# RX_Balun.net
KiCad netlist of a schematic drawn in Altium Designer
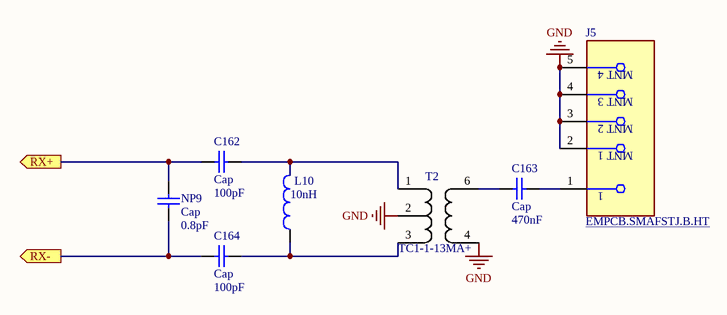
[diagram p0: RX Balun.SchDoc]

(export (version "E")
  (design (tool "Eeschema 10.0.6"))
  (components
    (comp (ref "C162")
      (value "Cap")
      (footprint "0402-A")
      (description "Capacitor")
      (fields (field (name "ALTIUM_VALUE") "100pF") (field (name "PUBLISHER") "Altium Limited"))
      (libsource (lib "Miscellaneous Devices") (part "Cap"))
    )
    (comp (ref "C163")
      (value "Cap")
      (footprint "0402-A")
      (description "Capacitor")
      (fields (field (name "ALTIUM_VALUE") "470nF") (field (name "PUBLISHER") "Altium Limited"))
      (libsource (lib "Miscellaneous Devices") (part "Cap"))
    )
    (comp (ref "C164")
      (value "Cap")
      (footprint "0402-A")
      (description "Capacitor")
      (fields (field (name "ALTIUM_VALUE") "100pF") (field (name "PUBLISHER") "Altium Limited"))
      (libsource (lib "Miscellaneous Devices") (part "Cap"))
    )
    (comp (ref "J5")
      (value "EMPCB.SMAFSTJ.B.HT")
      (footprint "FP-EMPCB_SMAFSTJ_B_HT-MFG")
      (description "CONN SMA JACK STR 50OHM EDGE MNT")
      (fields
        (field (name "OCTOPART") "https://octopart.com/empcb.smafstj.b.ht-taoglas-24204431")
        (field (name "MANUFACTURER") "Taoglas Limited")
      )
      (libsource (lib "Altium Content Vault") (part "c65b8a639cdaef1819ea20b5466f8fa"))
    )
    (comp (ref "L10")
      (value "10nH")
      (footprint "1608[0603]")
      (description "Inductor")
      (fields (field (name "PUBLISHER") "Altium Limited"))
      (libsource (lib "Miscellaneous Devices") (part "Inductor"))
    )
    (comp (ref "NP9")
      (value "Cap")
      (footprint "0402-A")
      (description "Capacitor")
      (fields (field (name "ALTIUM_VALUE") "0.8pF") (field (name "PUBLISHER") "Altium Limited"))
      (libsource (lib "Miscellaneous Devices") (part "Cap"))
    )
    (comp (ref "T2")
      (value "TC1-1-13MA+")
      (footprint "TC1-1-13MA+")
      (libsource (lib "TC1-1-13MA+") (part "TC1-1-13MA+"))
    )
  )
  (nets
    (net (code "1") (name "/RX+") (class "Default")
      (node (ref "C162") (pin "1") (pinfunction "1_1") (pintype "passive"))
      (node (ref "NP9") (pin "1") (pinfunction "1_1") (pintype "passive"))
    )
    (net (code "2") (name "/RX-") (class "Default")
      (node (ref "C164") (pin "1") (pinfunction "1_1") (pintype "passive"))
      (node (ref "NP9") (pin "2") (pinfunction "2_2") (pintype "passive"))
    )
    (net (code "3") (name "GND") (class "Default")
      (node (ref "J5") (pin "2") (pinfunction "MNT_1_2") (pintype "passive"))
      (node (ref "J5") (pin "3") (pinfunction "MNT_2_3") (pintype "passive"))
      (node (ref "J5") (pin "4") (pinfunction "MNT_3_4") (pintype "passive"))
      (node (ref "J5") (pin "5") (pinfunction "MNT_4_5") (pintype "passive"))
      (node (ref "T2") (pin "2") (pintype "passive"))
      (node (ref "T2") (pin "4") (pintype "passive"))
    )
    (net (code "4") (name "Net-(C162-Pad2)") (class "Default")
      (node (ref "C162") (pin "2") (pinfunction "2_2") (pintype "passive"))
      (node (ref "L10") (pin "2") (pinfunction "2_2") (pintype "passive"))
      (node (ref "T2") (pin "1") (pintype "passive"))
    )
    (net (code "5") (name "Net-(C163-Pad1)") (class "Default")
      (node (ref "C163") (pin "1") (pinfunction "1_1") (pintype "passive"))
      (node (ref "T2") (pin "6") (pintype "passive"))
    )
    (net (code "6") (name "Net-(C163-Pad2)") (class "Default")
      (node (ref "C163") (pin "2") (pinfunction "2_2") (pintype "passive"))
      (node (ref "J5") (pin "1") (pinfunction "1_1") (pintype "passive"))
    )
    (net (code "7") (name "Net-(C164-Pad2)") (class "Default")
      (node (ref "C164") (pin "2") (pinfunction "2_2") (pintype "passive"))
      (node (ref "L10") (pin "1") (pinfunction "1_1") (pintype "passive"))
      (node (ref "T2") (pin "3") (pintype "passive"))
    )
  )
)
